# JWpulsegen-V1.net
KiCad netlist of a schematic drawn in Altium Designer
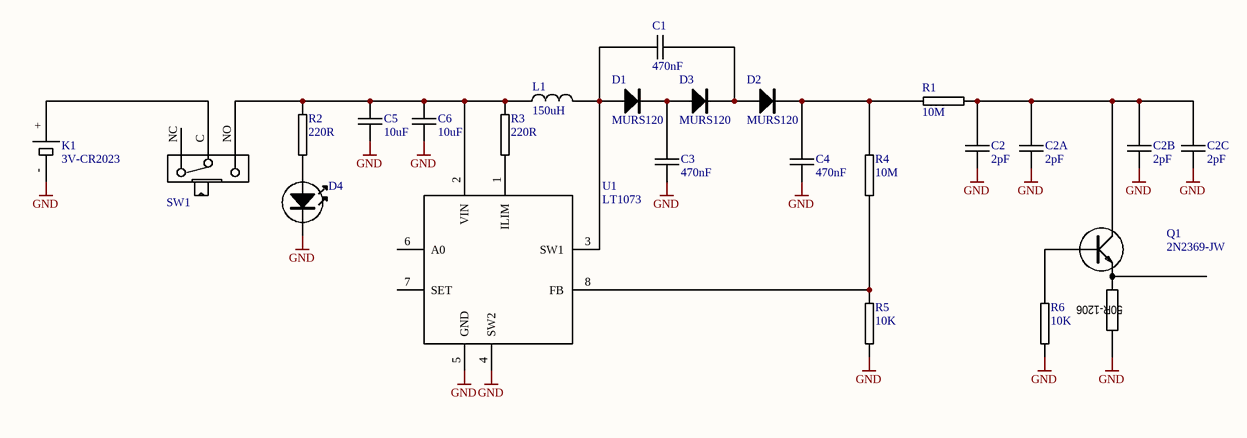
[diagram p0: JWpulsegen-V1.SchDoc]

(export (version "E")
  (design (tool "Eeschema 10.0.6"))
  (components
    (comp (ref "C1")
      (value "470nF")
      (footprint "1812C-GENERIC")
      (description "CAPACITOR 1812 CERAMIC")
      (libsource (lib "SMD Capacitors Other") (part "1812C-470nF-250V-X7R-MUR"))
    )
    (comp (ref "C2")
      (value "2pF")
      (footprint "0805C-GENERIC")
      (description "CAPACITOR 0805 CERAMIC")
      (fields (field (name "TOLERANCE") "±20%") (field (name "MANUFACTURER") "Panasonic - ECG"))
      (libsource (lib "vh_Altium Library") (part "0805C-10UF-6V3-X5R-PAN"))
    )
    (comp (ref "C2A")
      (value "2pF")
      (footprint "0805C-GENERIC")
      (description "CAPACITOR 0805 CERAMIC")
      (fields (field (name "TOLERANCE") "±20%") (field (name "MANUFACTURER") "Panasonic - ECG"))
      (libsource (lib "vh_Altium Library") (part "0805C-10UF-6V3-X5R-PAN"))
    )
    (comp (ref "C2B")
      (value "2pF")
      (footprint "0805C-GENERIC")
      (description "CAPACITOR 0805 CERAMIC")
      (fields (field (name "TOLERANCE") "±20%") (field (name "MANUFACTURER") "Panasonic - ECG"))
      (libsource (lib "vh_Altium Library") (part "0805C-10UF-6V3-X5R-PAN"))
    )
    (comp (ref "C2C")
      (value "2pF")
      (footprint "0805C-GENERIC")
      (description "CAPACITOR 0805 CERAMIC")
      (fields (field (name "TOLERANCE") "±20%") (field (name "MANUFACTURER") "Panasonic - ECG"))
      (libsource (lib "vh_Altium Library") (part "0805C-10UF-6V3-X5R-PAN"))
    )
    (comp (ref "C3")
      (value "470nF")
      (footprint "1812C-GENERIC")
      (description "CAPACITOR 1812 CERAMIC")
      (libsource (lib "SMD Capacitors Other") (part "1812C-470nF-250V-X7R-MUR"))
    )
    (comp (ref "C4")
      (value "470nF")
      (footprint "1812C-GENERIC")
      (description "CAPACITOR 1812 CERAMIC")
      (libsource (lib "SMD Capacitors Other") (part "1812C-470nF-250V-X7R-MUR"))
    )
    (comp (ref "C5")
      (value "10uF")
      (footprint "0805C-GENERIC")
      (description "CAPACITOR 0805 CERAMIC")
      (fields (field (name "TOLERANCE") "±20%") (field (name "MANUFACTURER") "Panasonic - ECG"))
      (libsource (lib "vh_Altium Library") (part "0805C-10UF-6V3-X5R-PAN"))
    )
    (comp (ref "C6")
      (value "10uF")
      (footprint "0805C-GENERIC")
      (description "CAPACITOR 0805 CERAMIC")
      (fields (field (name "TOLERANCE") "±20%") (field (name "MANUFACTURER") "Panasonic - ECG"))
      (libsource (lib "vh_Altium Library") (part "0805C-10UF-6V3-X5R-PAN"))
    )
    (comp (ref "D1")
      (value "MURS120")
      (footprint "DIODE-SMB")
      (description "DIODE")
      (libsource (lib "SMD Diodes") (part "MURS120"))
    )
    (comp (ref "D2")
      (value "MURS120")
      (footprint "DIODE-SMB")
      (description "DIODE")
      (libsource (lib "SMD Diodes") (part "MURS120"))
    )
    (comp (ref "D3")
      (value "MURS120")
      (footprint "DIODE-SMB")
      (description "DIODE")
      (libsource (lib "SMD Diodes") (part "MURS120"))
    )
    (comp (ref "D4")
      (value "LED-YELLOW-3MM")
      (footprint "LED-3MM-YELLOW")
      (libsource (lib "vh_Altium Library") (part "LED-YELLOW-3MM"))
    )
    (comp (ref "K1")
      (value "3V-CR2023")
      (footprint "BATCLIP-CR2032")
      (description "BU2032SM-HD-G")
      (libsource (lib "SMD Connectors") (part "BATCLIP-CR2032-SMD"))
    )
    (comp (ref "L1")
      (value "150uH")
      (footprint "TOKO-NR4018")
      (libsource (lib "SMD Magnetics") (part "150U-NR4018-TOKO"))
    )
    (comp (ref "Q1")
      (value "2N2369-JW")
      (footprint "JW2N2369")
      (libsource (lib "Specials") (part "2N2369-JW"))
    )
    (comp (ref "R1")
      (value "10M")
      (footprint "0805R-TBD")
      (description "RESISTOR 0805 VALUE TO BE DETERMINED")
      (libsource (lib "vh_Altium Library") (part "0805R-10M"))
    )
    (comp (ref "R2")
      (value "220R")
      (footprint "0805R-220")
      (description "RESISTOR 0805 1/4 WATT THIN FILM")
      (libsource (lib "vh_Altium Library") (part "0805R-220"))
    )
    (comp (ref "R3")
      (value "220R")
      (footprint "0805R-220")
      (description "RESISTOR 0805 1/4 WATT THIN FILM")
      (libsource (lib "vh_Altium Library") (part "0805R-220"))
    )
    (comp (ref "R4")
      (value "10M")
      (footprint "0805R-TBD")
      (description "RESISTOR 0805 VALUE TO BE DETERMINED")
      (libsource (lib "vh_Altium Library") (part "0805R-10M"))
    )
    (comp (ref "R5")
      (value "10K")
      (footprint "0805R-10K")
      (description "RESISTOR 0805 1/4 WATT THIN FILM")
      (libsource (lib "vh_Altium Library") (part "0805R-10K"))
    )
    (comp (ref "R6")
      (value "10K")
      (footprint "0805R-10K")
      (description "RESISTOR 0805 1/4 WATT THIN FILM")
      (libsource (lib "vh_Altium Library") (part "0805R-10K"))
    )
    (comp (ref "SW1")
      (value "SW-SPDT-CK-OS102011")
      (footprint "CK-OS102011")
      (description "SWITCH DPDT")
      (libsource (lib "Switches") (part "SW-SPDT-CK-OS102011"))
    )
    (comp (ref "U1") (value "LT1073") (footprint "SO8") (libsource (lib "IC Regulators") (part "LT1073")))
  )
  (nets
    (net (code "1") (name "GND") (class "Default")
      (node (ref "C2") (pin "2") (pintype "passive"))
      (node (ref "C2A") (pin "2") (pintype "passive"))
      (node (ref "C2B") (pin "2") (pintype "passive"))
      (node (ref "C2C") (pin "2") (pintype "passive"))
      (node (ref "C3") (pin "1") (pintype "passive"))
      (node (ref "C4") (pin "1") (pintype "passive"))
      (node (ref "C5") (pin "2") (pintype "passive"))
      (node (ref "C6") (pin "2") (pintype "passive"))
      (node (ref "D4") (pin "K") (pintype "passive"))
      (node (ref "K1") (pin "-") (pintype "passive"))
      (node (ref "Q1") (pin "G") (pintype "passive"))
      (node (ref "R5") (pin "2") (pintype "passive"))
      (node (ref "R6") (pin "2") (pintype "passive"))
      (node (ref "U1") (pin "4") (pinfunction "SW2_4") (pintype "passive"))
      (node (ref "U1") (pin "5") (pinfunction "GND_5") (pintype "passive"))
    )
    (net (code "2") (name "Net-(C1-Pad2)") (class "Default")
      (node (ref "C1") (pin "2") (pintype "passive"))
      (node (ref "D2") (pin "A") (pinfunction "A_A") (pintype "passive"))
      (node (ref "D3") (pin "K") (pinfunction "K_K") (pintype "passive"))
    )
    (net (code "3") (name "Net-(C2-Pad1)") (class "Default")
      (node (ref "C2") (pin "1") (pintype "passive"))
      (node (ref "C2A") (pin "1") (pintype "passive"))
      (node (ref "C2B") (pin "1") (pintype "passive"))
      (node (ref "C2C") (pin "1") (pintype "passive"))
      (node (ref "Q1") (pin "C") (pintype "passive"))
      (node (ref "R1") (pin "2") (pintype "passive"))
    )
    (net (code "4") (name "Net-(C3-Pad2)") (class "Default")
      (node (ref "C3") (pin "2") (pintype "passive"))
      (node (ref "D1") (pin "K") (pinfunction "K_K") (pintype "passive"))
      (node (ref "D3") (pin "A") (pinfunction "A_A") (pintype "passive"))
    )
    (net (code "5") (name "Net-(C4-Pad2)") (class "Default")
      (node (ref "C4") (pin "2") (pintype "passive"))
      (node (ref "D2") (pin "K") (pinfunction "K_K") (pintype "passive"))
      (node (ref "R1") (pin "1") (pintype "passive"))
      (node (ref "R4") (pin "1") (pintype "passive"))
    )
    (net (code "6") (name "Net-(D4-PadA)") (class "Default")
      (node (ref "D4") (pin "A") (pintype "passive"))
      (node (ref "R2") (pin "2") (pintype "passive"))
    )
    (net (code "7") (name "Net-(K1-Pad+)") (class "Default")
      (node (ref "K1") (pin "+") (pintype "passive"))
      (node (ref "SW1") (pin "C") (pintype "passive"))
    )
    (net (code "8") (name "Net-(Q1-PadB)") (class "Default")
      (node (ref "Q1") (pin "B") (pintype "passive"))
      (node (ref "R6") (pin "1") (pintype "passive"))
    )
    (net (code "9") (name "Net-(U1-FB)") (class "Default")
      (node (ref "R4") (pin "2") (pintype "passive"))
      (node (ref "R5") (pin "1") (pintype "passive"))
      (node (ref "U1") (pin "8") (pinfunction "FB_8") (pintype "passive"))
    )
    (net (code "10") (name "Net-(U1-ILIM)") (class "Default")
      (node (ref "R3") (pin "2") (pintype "passive"))
      (node (ref "U1") (pin "1") (pinfunction "ILIM_1") (pintype "passive"))
    )
    (net (code "11") (name "Net-(U1-SW1)") (class "Default")
      (node (ref "C1") (pin "1") (pintype "passive"))
      (node (ref "D1") (pin "A") (pinfunction "A_A") (pintype "passive"))
      (node (ref "L1") (pin "2") (pinfunction "2_2") (pintype "passive"))
      (node (ref "U1") (pin "3") (pinfunction "SW1_3") (pintype "passive"))
    )
    (net (code "12") (name "Net-(U1-VIN)") (class "Default")
      (node (ref "C5") (pin "1") (pintype "passive"))
      (node (ref "C6") (pin "1") (pintype "passive"))
      (node (ref "L1") (pin "1") (pinfunction "1_1") (pintype "passive"))
      (node (ref "R2") (pin "1") (pintype "passive"))
      (node (ref "R3") (pin "1") (pintype "passive"))
      (node (ref "SW1") (pin "NO") (pintype "passive"))
      (node (ref "U1") (pin "2") (pinfunction "VIN_2") (pintype "passive"))
    )
    (net (code "13") (name "unconnected-(SW1-NC2-PadNC)") (class "Default")
      (node (ref "SW1") (pin "NC") (pinfunction "NC2_NC") (pintype "passive"))
    )
    (net (code "14") (name "unconnected-(U1-A0-Pad6)") (class "Default")
      (node (ref "U1") (pin "6") (pinfunction "A0_6") (pintype "passive"))
    )
    (net (code "15") (name "unconnected-(U1-SET-Pad7)") (class "Default")
      (node (ref "U1") (pin "7") (pinfunction "SET_7") (pintype "passive"))
    )
  )
)
